# FPC_test_-_connector_side.net
KiCad netlist of a schematic drawn in Altium Designer
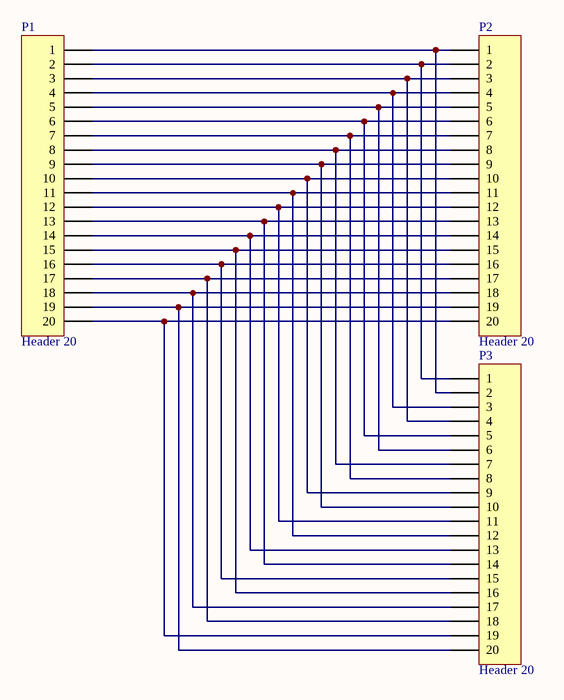
[diagram p0: FPC test - connector side.SchDoc]

(export (version "E")
  (design (tool "Eeschema 10.0.6"))
  (components
    (comp (ref "P1")
      (value "Header 20")
      (footprint "HDR1X20")
      (description "Header, 20-Pin")
      (fields (field (name "PUBLISHER") "Altium Limited"))
      (libsource (lib "") (part "Header 20_1"))
    )
    (comp (ref "P2")
      (value "Header 20")
      (footprint "2-1734248-0")
      (description "Header, 20-Pin")
      (fields (field (name "PUBLISHER") "Altium Limited"))
      (libsource (lib "Miscellaneous Connectors") (part "Header 20"))
    )
    (comp (ref "P3")
      (value "Header 20")
      (footprint "SLW16S-1C7LF")
      (description "Header, 20-Pin")
      (fields (field (name "PUBLISHER") "Altium Limited"))
      (libsource (lib "Miscellaneous Connectors") (part "Header 20"))
    )
  )
  (nets
    (net (code "1") (name "Net-(P1-Pad1)") (class "Default")
      (node (ref "P1") (pin "1") (pinfunction "1_1") (pintype "passive"))
      (node (ref "P2") (pin "1") (pinfunction "1_1") (pintype "passive"))
      (node (ref "P3") (pin "2") (pinfunction "2_2") (pintype "passive"))
    )
    (net (code "2") (name "Net-(P1-Pad2)") (class "Default")
      (node (ref "P1") (pin "2") (pinfunction "2_2") (pintype "passive"))
      (node (ref "P2") (pin "2") (pinfunction "2_2") (pintype "passive"))
      (node (ref "P3") (pin "1") (pinfunction "1_1") (pintype "passive"))
    )
    (net (code "3") (name "Net-(P1-Pad3)") (class "Default")
      (node (ref "P1") (pin "3") (pinfunction "3_3") (pintype "passive"))
      (node (ref "P2") (pin "3") (pinfunction "3_3") (pintype "passive"))
      (node (ref "P3") (pin "4") (pinfunction "4_4") (pintype "passive"))
    )
    (net (code "4") (name "Net-(P1-Pad4)") (class "Default")
      (node (ref "P1") (pin "4") (pinfunction "4_4") (pintype "passive"))
      (node (ref "P2") (pin "4") (pinfunction "4_4") (pintype "passive"))
      (node (ref "P3") (pin "3") (pinfunction "3_3") (pintype "passive"))
    )
    (net (code "5") (name "Net-(P1-Pad5)") (class "Default")
      (node (ref "P1") (pin "5") (pinfunction "5_5") (pintype "passive"))
      (node (ref "P2") (pin "5") (pinfunction "5_5") (pintype "passive"))
      (node (ref "P3") (pin "6") (pinfunction "6_6") (pintype "passive"))
    )
    (net (code "6") (name "Net-(P1-Pad6)") (class "Default")
      (node (ref "P1") (pin "6") (pinfunction "6_6") (pintype "passive"))
      (node (ref "P2") (pin "6") (pinfunction "6_6") (pintype "passive"))
      (node (ref "P3") (pin "5") (pinfunction "5_5") (pintype "passive"))
    )
    (net (code "7") (name "Net-(P1-Pad7)") (class "Default")
      (node (ref "P1") (pin "7") (pinfunction "7_7") (pintype "passive"))
      (node (ref "P2") (pin "7") (pinfunction "7_7") (pintype "passive"))
      (node (ref "P3") (pin "8") (pinfunction "8_8") (pintype "passive"))
    )
    (net (code "8") (name "Net-(P1-Pad8)") (class "Default")
      (node (ref "P1") (pin "8") (pinfunction "8_8") (pintype "passive"))
      (node (ref "P2") (pin "8") (pinfunction "8_8") (pintype "passive"))
      (node (ref "P3") (pin "7") (pinfunction "7_7") (pintype "passive"))
    )
    (net (code "9") (name "Net-(P1-Pad9)") (class "Default")
      (node (ref "P1") (pin "9") (pinfunction "9_9") (pintype "passive"))
      (node (ref "P2") (pin "9") (pinfunction "9_9") (pintype "passive"))
      (node (ref "P3") (pin "10") (pinfunction "10_10") (pintype "passive"))
    )
    (net (code "10") (name "Net-(P1-Pad10)") (class "Default")
      (node (ref "P1") (pin "10") (pinfunction "10_10") (pintype "passive"))
      (node (ref "P2") (pin "10") (pinfunction "10_10") (pintype "passive"))
      (node (ref "P3") (pin "9") (pinfunction "9_9") (pintype "passive"))
    )
    (net (code "11") (name "Net-(P1-Pad11)") (class "Default")
      (node (ref "P1") (pin "11") (pinfunction "11_11") (pintype "passive"))
      (node (ref "P2") (pin "11") (pinfunction "11_11") (pintype "passive"))
      (node (ref "P3") (pin "12") (pinfunction "12_12") (pintype "passive"))
    )
    (net (code "12") (name "Net-(P1-Pad12)") (class "Default")
      (node (ref "P1") (pin "12") (pinfunction "12_12") (pintype "passive"))
      (node (ref "P2") (pin "12") (pinfunction "12_12") (pintype "passive"))
      (node (ref "P3") (pin "11") (pinfunction "11_11") (pintype "passive"))
    )
    (net (code "13") (name "Net-(P1-Pad13)") (class "Default")
      (node (ref "P1") (pin "13") (pinfunction "13_13") (pintype "passive"))
      (node (ref "P2") (pin "13") (pinfunction "13_13") (pintype "passive"))
      (node (ref "P3") (pin "14") (pinfunction "14_14") (pintype "passive"))
    )
    (net (code "14") (name "Net-(P1-Pad14)") (class "Default")
      (node (ref "P1") (pin "14") (pinfunction "14_14") (pintype "passive"))
      (node (ref "P2") (pin "14") (pinfunction "14_14") (pintype "passive"))
      (node (ref "P3") (pin "13") (pinfunction "13_13") (pintype "passive"))
    )
    (net (code "15") (name "Net-(P1-Pad15)") (class "Default")
      (node (ref "P1") (pin "15") (pinfunction "15_15") (pintype "passive"))
      (node (ref "P2") (pin "15") (pinfunction "15_15") (pintype "passive"))
      (node (ref "P3") (pin "16") (pinfunction "16_16") (pintype "passive"))
    )
    (net (code "16") (name "Net-(P1-Pad16)") (class "Default")
      (node (ref "P1") (pin "16") (pinfunction "16_16") (pintype "passive"))
      (node (ref "P2") (pin "16") (pinfunction "16_16") (pintype "passive"))
      (node (ref "P3") (pin "15") (pinfunction "15_15") (pintype "passive"))
    )
    (net (code "17") (name "Net-(P1-Pad17)") (class "Default")
      (node (ref "P1") (pin "17") (pinfunction "17_17") (pintype "passive"))
      (node (ref "P2") (pin "17") (pinfunction "17_17") (pintype "passive"))
      (node (ref "P3") (pin "18") (pinfunction "18_18") (pintype "passive"))
    )
    (net (code "18") (name "Net-(P1-Pad18)") (class "Default")
      (node (ref "P1") (pin "18") (pinfunction "18_18") (pintype "passive"))
      (node (ref "P2") (pin "18") (pinfunction "18_18") (pintype "passive"))
      (node (ref "P3") (pin "17") (pinfunction "17_17") (pintype "passive"))
    )
    (net (code "19") (name "Net-(P1-Pad19)") (class "Default")
      (node (ref "P1") (pin "19") (pinfunction "19_19") (pintype "passive"))
      (node (ref "P2") (pin "19") (pinfunction "19_19") (pintype "passive"))
      (node (ref "P3") (pin "20") (pinfunction "20_20") (pintype "passive"))
    )
    (net (code "20") (name "Net-(P1-Pad20)") (class "Default")
      (node (ref "P1") (pin "20") (pinfunction "20_20") (pintype "passive"))
      (node (ref "P2") (pin "20") (pinfunction "20_20") (pintype "passive"))
      (node (ref "P3") (pin "19") (pinfunction "19_19") (pintype "passive"))
    )
  )
)
